# rapidshark-lipo-sensor-mk-1_0.net
KiCad netlist of a schematic drawn in EAGLE
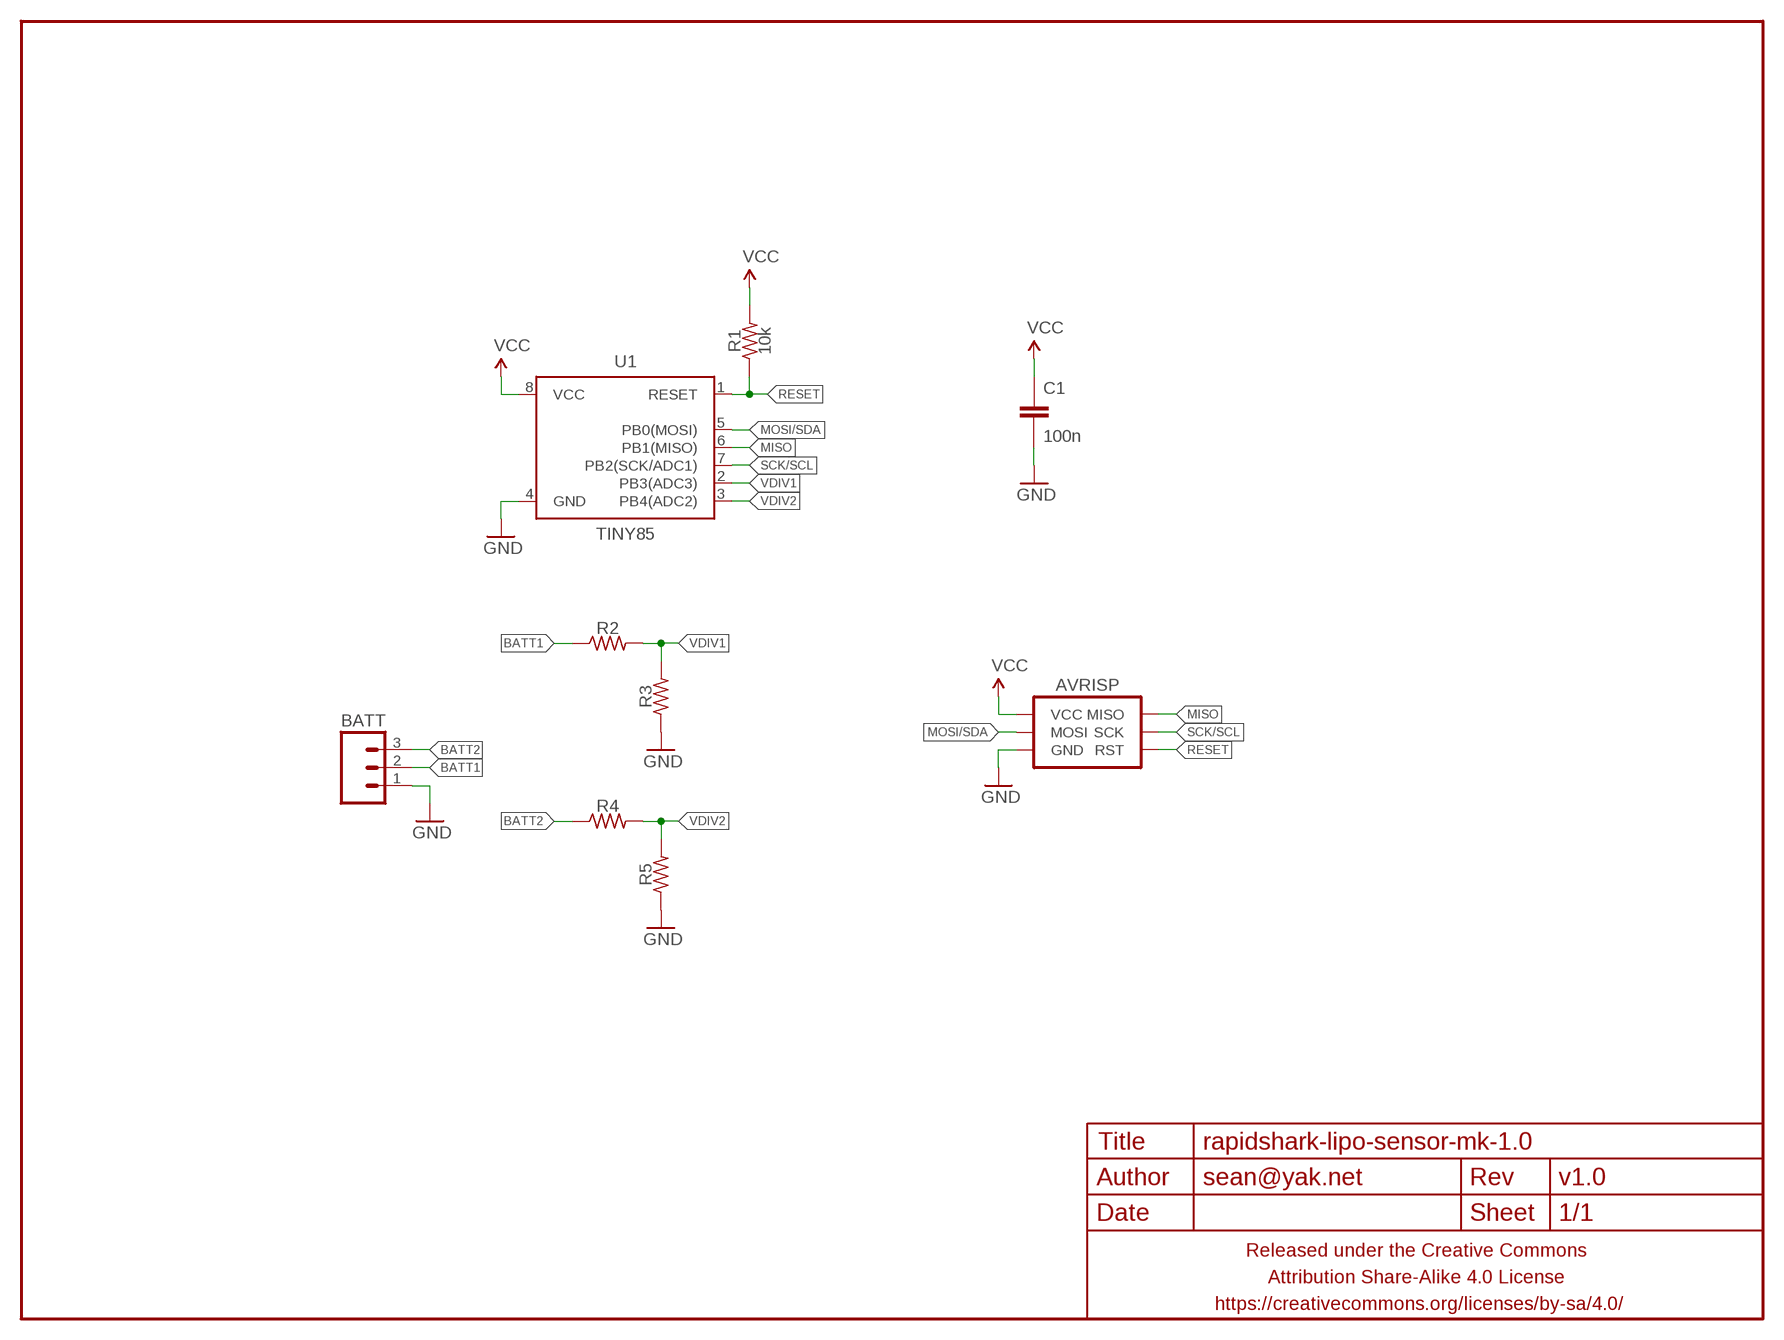
[diagram p0: schematic, sheet 1]

(export (version "E")
  (design (tool "Eeschema 10.0.6"))
  (components
    (comp (ref "AVRISP")
      (value "AVR_SPI_PRG_6PTH_INLINE_I2C")
      (footprint "eagle-import:AVR_ISP_INLINE_PTH_I2C")
      (libsource (lib "eagle-import") (part "AVR_SPI_PRG_6PTH_INLINE_I2C"))
    )
    (comp (ref "BATT")
      (value "M03PTH-CENTERED")
      (footprint "eagle-import:1X03-CENTERED")
      (libsource (lib "eagle-import") (part "M03PTH-CENTERED"))
    )
    (comp (ref "C1")
      (value "100n")
      (footprint "eagle-import:C025-024X044")
      (libsource (lib "eagle-import") (part "CAPACITOR-CERAMIC025-024X044"))
    )
    (comp (ref "FRAME1")
      (value "FRAME-LETTERNO_PACKAGE")
      (footprint "eagle-import:DUMMY")
      (fields (field (name "DESIGNER") "sean@yak.net") (field (name "VERSION") "v1.0"))
      (libsource (lib "eagle-import") (part "FRAME-LETTERNO_PACKAGE"))
    )
    (comp (ref "R1")
      (value "10k")
      (footprint "eagle-import:RESISTOR-AXIAL-PTH-7.62MM")
      (libsource (lib "eagle-import") (part "RESISTORPTH-AXIAL-7.62MM"))
    )
    (comp (ref "R2")
      (value "RESISTORPTH-AXIAL-7.62MM")
      (footprint "eagle-import:RESISTOR-AXIAL-PTH-7.62MM")
      (libsource (lib "eagle-import") (part "RESISTORPTH-AXIAL-7.62MM"))
    )
    (comp (ref "R3")
      (value "RESISTORPTH-AXIAL-7.62MM")
      (footprint "eagle-import:RESISTOR-AXIAL-PTH-7.62MM")
      (libsource (lib "eagle-import") (part "RESISTORPTH-AXIAL-7.62MM"))
    )
    (comp (ref "R4")
      (value "RESISTORPTH-AXIAL-7.62MM")
      (footprint "eagle-import:RESISTOR-AXIAL-PTH-7.62MM")
      (libsource (lib "eagle-import") (part "RESISTORPTH-AXIAL-7.62MM"))
    )
    (comp (ref "R5")
      (value "RESISTORPTH-AXIAL-7.62MM")
      (footprint "eagle-import:RESISTOR-AXIAL-PTH-7.62MM")
      (libsource (lib "eagle-import") (part "RESISTORPTH-AXIAL-7.62MM"))
    )
    (comp (ref "U1")
      (value "TINY85")
      (footprint "eagle-import:DIP08")
      (libsource (lib "eagle-import") (part "ATTINY45TINY85-20-DIP"))
    )
  )
  (nets
    (net (code "1") (name "BATT1") (class "Default")
      (node (ref "BATT") (pin "2") (pinfunction "2_2") (pintype "passive"))
      (node (ref "R2") (pin "P$1") (pinfunction "1_P$1") (pintype "passive"))
    )
    (net (code "2") (name "BATT2") (class "Default")
      (node (ref "BATT") (pin "3") (pinfunction "3_3") (pintype "passive"))
      (node (ref "R4") (pin "P$1") (pinfunction "1_P$1") (pintype "passive"))
    )
    (net (code "3") (name "GND") (class "Default")
      (node (ref "AVRISP") (pin "GND") (pinfunction "GND_GND") (pintype "passive"))
      (node (ref "BATT") (pin "1") (pinfunction "1_1") (pintype "passive"))
      (node (ref "C1") (pin "2") (pinfunction "2_2") (pintype "passive"))
      (node (ref "R3") (pin "P$1") (pinfunction "1_P$1") (pintype "passive"))
      (node (ref "R5") (pin "P$1") (pinfunction "1_P$1") (pintype "passive"))
      (node (ref "U1") (pin "4") (pinfunction "GND_4") (pintype "bidirectional"))
    )
    (net (code "4") (name "MISO") (class "Default")
      (node (ref "AVRISP") (pin "MISO") (pinfunction "MISO_MISO") (pintype "passive"))
      (node (ref "U1") (pin "6") (pinfunction "PB1(MISO)_6") (pintype "bidirectional"))
    )
    (net (code "5") (name "MOSI{slash}SDA") (class "Default")
      (node (ref "AVRISP") (pin "MOSI") (pinfunction "MOSI_MOSI") (pintype "passive"))
      (node (ref "U1") (pin "5") (pinfunction "PB0(MOSI)_5") (pintype "bidirectional"))
    )
    (net (code "6") (name "RESET") (class "Default")
      (node (ref "AVRISP") (pin "RESET") (pinfunction "RST_RESET") (pintype "passive"))
      (node (ref "R1") (pin "P$1") (pinfunction "1_P$1") (pintype "passive"))
      (node (ref "U1") (pin "1") (pinfunction "RESET_1") (pintype "bidirectional"))
    )
    (net (code "7") (name "SCK{slash}SCL") (class "Default")
      (node (ref "AVRISP") (pin "SCK") (pinfunction "SCK_SCK") (pintype "passive"))
      (node (ref "U1") (pin "7") (pinfunction "PB2(SCK/ADC1)_7") (pintype "bidirectional"))
    )
    (net (code "8") (name "VCC") (class "Default")
      (node (ref "AVRISP") (pin "VCC") (pinfunction "VCC_VCC") (pintype "passive"))
      (node (ref "C1") (pin "1") (pinfunction "1_1") (pintype "passive"))
      (node (ref "R1") (pin "P$2") (pinfunction "2_P$2") (pintype "passive"))
      (node (ref "U1") (pin "8") (pinfunction "VCC_8") (pintype "bidirectional"))
    )
    (net (code "9") (name "VDIV1") (class "Default")
      (node (ref "R2") (pin "P$2") (pinfunction "2_P$2") (pintype "passive"))
      (node (ref "R3") (pin "P$2") (pinfunction "2_P$2") (pintype "passive"))
      (node (ref "U1") (pin "2") (pinfunction "PB3(ADC3)_2") (pintype "bidirectional"))
    )
    (net (code "10") (name "VDIV2") (class "Default")
      (node (ref "R4") (pin "P$2") (pinfunction "2_P$2") (pintype "passive"))
      (node (ref "R5") (pin "P$2") (pinfunction "2_P$2") (pintype "passive"))
      (node (ref "U1") (pin "3") (pinfunction "PB4(ADC2)_3") (pintype "bidirectional"))
    )
  )
)
